# distortion3_redraw.net
KiCad netlist of a schematic drawn in EAGLE
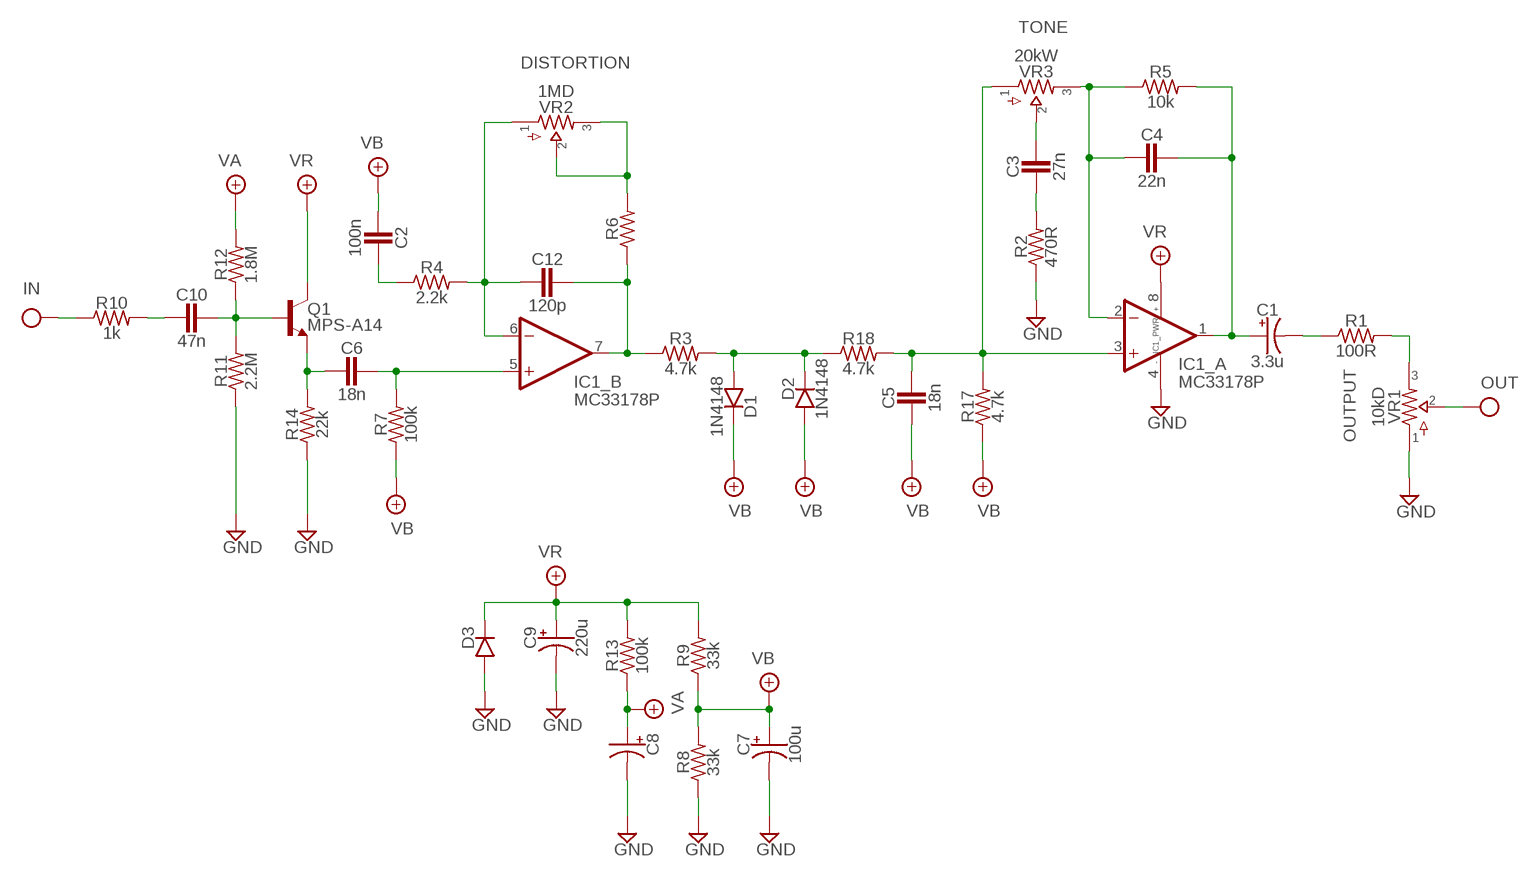
[diagram p0: schematic, sheet 1]

(export (version "E")
  (design (tool "Eeschema 10.0.6"))
  (components
    (comp (ref "C1")
      (value "3.3u")
      (footprint "eagle-import:050_020")
      (libsource (lib "eagle-import") (part "0500"))
    )
    (comp (ref "C2")
      (value "100n")
      (footprint "eagle-import:BOX_SMALL")
      (libsource (lib "eagle-import") (part "CER/FILMBOX.1"))
    )
    (comp (ref "C3")
      (value "27n")
      (footprint "eagle-import:BOX_SMALL")
      (libsource (lib "eagle-import") (part "CER/FILMBOX.1"))
    )
    (comp (ref "C4")
      (value "22n")
      (footprint "eagle-import:BOX_SMALL")
      (libsource (lib "eagle-import") (part "CER/FILMBOX.1"))
    )
    (comp (ref "C5")
      (value "18n")
      (footprint "eagle-import:BOX_SMALL")
      (libsource (lib "eagle-import") (part "CER/FILMBOX.1"))
    )
    (comp (ref "C6")
      (value "18n")
      (footprint "eagle-import:BOX_SMALL")
      (libsource (lib "eagle-import") (part "CER/FILMBOX.1"))
    )
    (comp (ref "C7")
      (value "100u")
      (footprint "eagle-import:050_020")
      (libsource (lib "eagle-import") (part "0500"))
    )
    (comp (ref "C8")
      (value "0500")
      (footprint "eagle-import:050_020")
      (libsource (lib "eagle-import") (part "0500"))
    )
    (comp (ref "C9")
      (value "220u")
      (footprint "eagle-import:050_020")
      (libsource (lib "eagle-import") (part "0500"))
    )
    (comp (ref "C10")
      (value "47n")
      (footprint "eagle-import:BOX_SMALL")
      (libsource (lib "eagle-import") (part "CER/FILMBOX.1"))
    )
    (comp (ref "C12")
      (value "120p")
      (footprint "eagle-import:BOX_SMALL")
      (libsource (lib "eagle-import") (part "CER/FILMBOX.1"))
    )
    (comp (ref "D1")
      (value "1N4148")
      (footprint "eagle-import:DO35-2")
      (libsource (lib "eagle-import") (part "DO35.2"))
    )
    (comp (ref "D2")
      (value "1N4148")
      (footprint "eagle-import:DO35-2")
      (libsource (lib "eagle-import") (part "DO35.2"))
    )
    (comp (ref "D3")
      (value "DO35.2")
      (footprint "eagle-import:DO35-2")
      (libsource (lib "eagle-import") (part "DO35.2"))
    )
    (comp (ref "IC1")
      (value "MC33178P")
      (footprint "eagle-import:DIL0")
      (libsource (lib "eagle-import") (part "DUALTH"))
    )
    (comp (ref "Q1")
      (value "MPS-A14")
      (footprint "eagle-import:TO92-")
      (libsource (lib "eagle-import") (part "2N3904"))
    )
    (comp (ref "R1")
      (value "100R")
      (footprint "eagle-import:R0207_3")
      (libsource (lib "eagle-import") (part "R_.3B"))
    )
    (comp (ref "R2")
      (value "470R")
      (footprint "eagle-import:R0207_3")
      (libsource (lib "eagle-import") (part "R_.3B"))
    )
    (comp (ref "R3")
      (value "4.7k")
      (footprint "eagle-import:R0207_3")
      (libsource (lib "eagle-import") (part "R_.3B"))
    )
    (comp (ref "R4")
      (value "2.2k")
      (footprint "eagle-import:R0207_3")
      (libsource (lib "eagle-import") (part "R_.3B"))
    )
    (comp (ref "R5")
      (value "10k")
      (footprint "eagle-import:R0207_3")
      (libsource (lib "eagle-import") (part "R_.3B"))
    )
    (comp (ref "R6")
      (value "R_.3B")
      (footprint "eagle-import:R0207_3")
      (libsource (lib "eagle-import") (part "R_.3B"))
    )
    (comp (ref "R7")
      (value "100k")
      (footprint "eagle-import:R0207_3")
      (libsource (lib "eagle-import") (part "R_.3B"))
    )
    (comp (ref "R8")
      (value "33k")
      (footprint "eagle-import:R0207_3")
      (libsource (lib "eagle-import") (part "R_.3B"))
    )
    (comp (ref "R9")
      (value "33k")
      (footprint "eagle-import:R0207_3")
      (libsource (lib "eagle-import") (part "R_.3B"))
    )
    (comp (ref "R10")
      (value "1k")
      (footprint "eagle-import:R0207_3")
      (libsource (lib "eagle-import") (part "R_.3B"))
    )
    (comp (ref "R11")
      (value "2.2M")
      (footprint "eagle-import:R0207_3")
      (libsource (lib "eagle-import") (part "R_.3B"))
    )
    (comp (ref "R12")
      (value "1.8M")
      (footprint "eagle-import:R0207_3")
      (libsource (lib "eagle-import") (part "R_.3B"))
    )
    (comp (ref "R13")
      (value "100k")
      (footprint "eagle-import:R0207_3")
      (libsource (lib "eagle-import") (part "R_.3B"))
    )
    (comp (ref "R14")
      (value "22k")
      (footprint "eagle-import:R0207_3")
      (libsource (lib "eagle-import") (part "R_.3B"))
    )
    (comp (ref "R17")
      (value "4.7k")
      (footprint "eagle-import:R0207_3")
      (libsource (lib "eagle-import") (part "R_.3B"))
    )
    (comp (ref "R18")
      (value "4.7k")
      (footprint "eagle-import:R0207_3")
      (libsource (lib "eagle-import") (part "R_.3B"))
    )
    (comp (ref "VR1")
      (value "10kD")
      (footprint "eagle-import:16MM")
      (libsource (lib "eagle-import") (part "POTS16MM"))
    )
    (comp (ref "VR2")
      (value "1MD")
      (footprint "eagle-import:16MM")
      (libsource (lib "eagle-import") (part "POTS16MM"))
    )
    (comp (ref "VR3")
      (value "20kW")
      (footprint "eagle-import:16MM")
      (libsource (lib "eagle-import") (part "POTS16MM"))
    )
  )
  (nets
    (net (code "1") (name "GND") (class "Default")
      (node (ref "C7") (pin "-") (pinfunction "-_-") (pintype "passive"))
      (node (ref "C8") (pin "-") (pinfunction "-_-") (pintype "passive"))
      (node (ref "C9") (pin "-") (pinfunction "-_-") (pintype "passive"))
      (node (ref "D3") (pin "A") (pinfunction "A_A") (pintype "passive"))
      (node (ref "IC1") (pin "4") (pinfunction "V-_4") (pintype "power_in"))
      (node (ref "R11") (pin "1") (pinfunction "1_1") (pintype "passive"))
      (node (ref "R14") (pin "1") (pinfunction "1_1") (pintype "passive"))
      (node (ref "R2") (pin "1") (pinfunction "1_1") (pintype "passive"))
      (node (ref "R8") (pin "1") (pinfunction "1_1") (pintype "passive"))
      (node (ref "VR1") (pin "1") (pinfunction "1_1") (pintype "passive"))
    )
    (net (code "2") (name "IN") (class "Default")
      (node (ref "R10") (pin "1") (pinfunction "1_1") (pintype "passive"))
    )
    (net (code "3") (name "Net-(C1-Pad-)") (class "Default")
      (node (ref "C1") (pin "-") (pinfunction "-_-") (pintype "passive"))
      (node (ref "R1") (pin "1") (pinfunction "1_1") (pintype "passive"))
    )
    (net (code "4") (name "Net-(C2-Pad2)") (class "Default")
      (node (ref "C2") (pin "2") (pinfunction "2_2") (pintype "passive"))
      (node (ref "R4") (pin "1") (pinfunction "1_1") (pintype "passive"))
    )
    (net (code "5") (name "Net-(C3-Pad1)") (class "Default")
      (node (ref "C3") (pin "1") (pinfunction "1_1") (pintype "passive"))
      (node (ref "R2") (pin "2") (pinfunction "2_2") (pintype "passive"))
    )
    (net (code "6") (name "Net-(C3-Pad2)") (class "Default")
      (node (ref "C3") (pin "2") (pinfunction "2_2") (pintype "passive"))
      (node (ref "VR3") (pin "2") (pinfunction "2_2") (pintype "passive"))
    )
    (net (code "7") (name "Net-(C10-Pad2)") (class "Default")
      (node (ref "C10") (pin "2") (pinfunction "2_2") (pintype "passive"))
      (node (ref "R10") (pin "2") (pinfunction "2_2") (pintype "passive"))
    )
    (net (code "8") (name "Net-(D1-PadA)") (class "Default")
      (node (ref "D1") (pin "A") (pinfunction "A_A") (pintype "passive"))
      (node (ref "D2") (pin "C") (pinfunction "C_C") (pintype "passive"))
      (node (ref "R18") (pin "1") (pinfunction "1_1") (pintype "passive"))
      (node (ref "R3") (pin "2") (pinfunction "2_2") (pintype "passive"))
    )
    (net (code "9") (name "Net-(IC1A-+IN)") (class "Default")
      (node (ref "C5") (pin "2") (pinfunction "2_2") (pintype "passive"))
      (node (ref "IC1") (pin "3") (pinfunction "+IN_3") (pintype "input"))
      (node (ref "R17") (pin "2") (pinfunction "2_2") (pintype "passive"))
      (node (ref "R18") (pin "2") (pinfunction "2_2") (pintype "passive"))
      (node (ref "VR3") (pin "1") (pinfunction "1_1") (pintype "passive"))
    )
    (net (code "10") (name "Net-(IC1A--IN)") (class "Default")
      (node (ref "C4") (pin "1") (pinfunction "1_1") (pintype "passive"))
      (node (ref "IC1") (pin "2") (pinfunction "-IN_2") (pintype "input"))
      (node (ref "R5") (pin "1") (pinfunction "1_1") (pintype "passive"))
      (node (ref "VR3") (pin "3") (pinfunction "3_3") (pintype "passive"))
    )
    (net (code "11") (name "Net-(IC1A-OUT)") (class "Default")
      (node (ref "C1") (pin "+") (pinfunction "+_+") (pintype "passive"))
      (node (ref "C4") (pin "2") (pinfunction "2_2") (pintype "passive"))
      (node (ref "IC1") (pin "1") (pinfunction "OUT_1") (pintype "output"))
      (node (ref "R5") (pin "2") (pinfunction "2_2") (pintype "passive"))
    )
    (net (code "12") (name "Net-(IC1B-+IN)") (class "Default")
      (node (ref "C6") (pin "2") (pinfunction "2_2") (pintype "passive"))
      (node (ref "IC1") (pin "5") (pinfunction "+IN_5") (pintype "input"))
      (node (ref "R7") (pin "2") (pinfunction "2_2") (pintype "passive"))
    )
    (net (code "13") (name "Net-(IC1B--IN)") (class "Default")
      (node (ref "C12") (pin "1") (pinfunction "1_1") (pintype "passive"))
      (node (ref "IC1") (pin "6") (pinfunction "-IN_6") (pintype "input"))
      (node (ref "R4") (pin "2") (pinfunction "2_2") (pintype "passive"))
      (node (ref "VR2") (pin "1") (pinfunction "1_1") (pintype "passive"))
    )
    (net (code "14") (name "Net-(IC1B-OUT)") (class "Default")
      (node (ref "C12") (pin "2") (pinfunction "2_2") (pintype "passive"))
      (node (ref "IC1") (pin "7") (pinfunction "OUT_7") (pintype "output"))
      (node (ref "R3") (pin "1") (pinfunction "1_1") (pintype "passive"))
      (node (ref "R6") (pin "1") (pinfunction "1_1") (pintype "passive"))
    )
    (net (code "15") (name "Net-(Q1-B)") (class "Default")
      (node (ref "C10") (pin "1") (pinfunction "1_1") (pintype "passive"))
      (node (ref "Q1") (pin "2") (pinfunction "B_2") (pintype "passive"))
      (node (ref "R11") (pin "2") (pinfunction "2_2") (pintype "passive"))
      (node (ref "R12") (pin "1") (pinfunction "1_1") (pintype "passive"))
    )
    (net (code "16") (name "Net-(Q1-E)") (class "Default")
      (node (ref "C6") (pin "1") (pinfunction "1_1") (pintype "passive"))
      (node (ref "Q1") (pin "3") (pinfunction "E_3") (pintype "passive"))
      (node (ref "R14") (pin "2") (pinfunction "2_2") (pintype "passive"))
    )
    (net (code "17") (name "Net-(R1-Pad2)") (class "Default")
      (node (ref "R1") (pin "2") (pinfunction "2_2") (pintype "passive"))
      (node (ref "VR1") (pin "3") (pinfunction "3_3") (pintype "passive"))
    )
    (net (code "18") (name "Net-(R6-Pad2)") (class "Default")
      (node (ref "R6") (pin "2") (pinfunction "2_2") (pintype "passive"))
      (node (ref "VR2") (pin "2") (pinfunction "2_2") (pintype "passive"))
      (node (ref "VR2") (pin "3") (pinfunction "3_3") (pintype "passive"))
    )
    (net (code "19") (name "OUT") (class "Default")
      (node (ref "VR1") (pin "2") (pinfunction "2_2") (pintype "passive"))
    )
    (net (code "20") (name "VA") (class "Default")
      (node (ref "C8") (pin "+") (pinfunction "+_+") (pintype "passive"))
      (node (ref "R12") (pin "2") (pinfunction "2_2") (pintype "passive"))
      (node (ref "R13") (pin "1") (pinfunction "1_1") (pintype "passive"))
    )
    (net (code "21") (name "VB") (class "Default")
      (node (ref "C2") (pin "1") (pinfunction "1_1") (pintype "passive"))
      (node (ref "C5") (pin "1") (pinfunction "1_1") (pintype "passive"))
      (node (ref "C7") (pin "+") (pinfunction "+_+") (pintype "passive"))
      (node (ref "D1") (pin "C") (pinfunction "C_C") (pintype "passive"))
      (node (ref "D2") (pin "A") (pinfunction "A_A") (pintype "passive"))
      (node (ref "R17") (pin "1") (pinfunction "1_1") (pintype "passive"))
      (node (ref "R7") (pin "1") (pinfunction "1_1") (pintype "passive"))
      (node (ref "R8") (pin "2") (pinfunction "2_2") (pintype "passive"))
      (node (ref "R9") (pin "1") (pinfunction "1_1") (pintype "passive"))
    )
    (net (code "22") (name "VR") (class "Default")
      (node (ref "C9") (pin "+") (pinfunction "+_+") (pintype "passive"))
      (node (ref "D3") (pin "C") (pinfunction "C_C") (pintype "passive"))
      (node (ref "IC1") (pin "8") (pinfunction "V+_8") (pintype "power_in"))
      (node (ref "Q1") (pin "1") (pinfunction "C_1") (pintype "passive"))
      (node (ref "R13") (pin "2") (pinfunction "2_2") (pintype "passive"))
      (node (ref "R9") (pin "2") (pinfunction "2_2") (pintype "passive"))
    )
  )
)
